# Microcontroller_rev2.net
KiCad netlist of a schematic drawn in Altium Designer
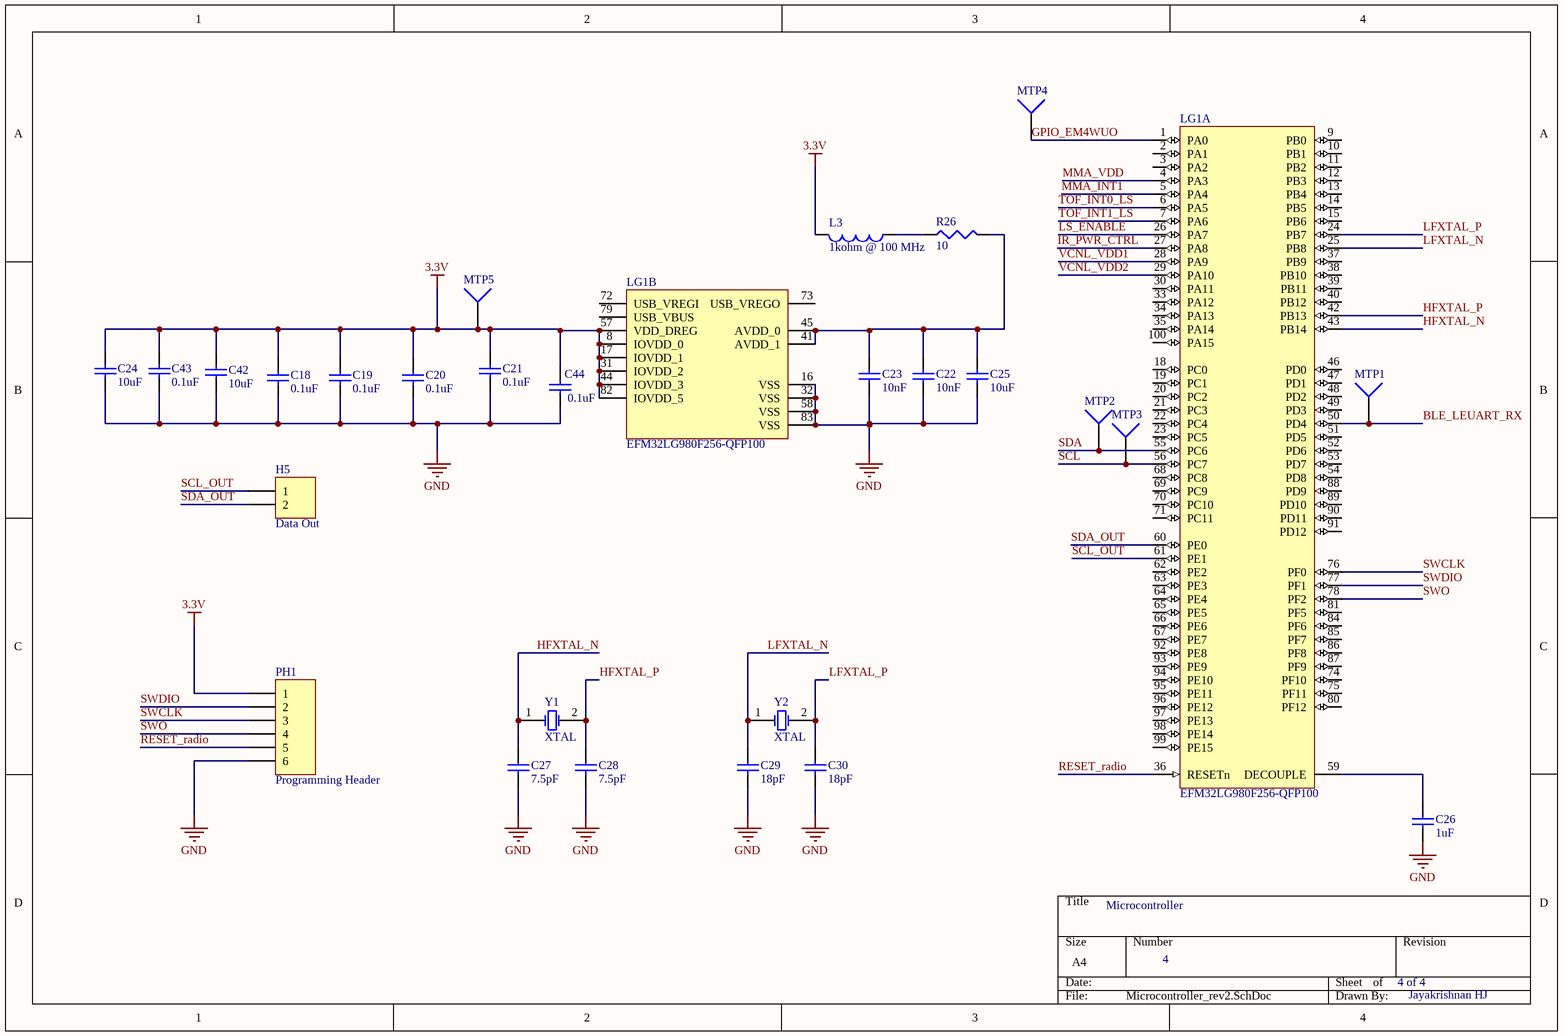
[diagram p0: Microcontroller_rev2.SchDoc]

(export (version "E")
  (design (tool "Eeschema 10.0.6"))
  (components
    (comp (ref "C18")
      (value "0.1uF")
      (footprint "1608[0603]")
      (description "CAP CER 0.1UF 10V X7R 0603")
      (fields (field (name "DIGIKEY PART NO") "399-1095-1-ND") (field (name "MANUFACTURER") "KEMET"))
      (libsource (lib "Miscellaneous Devices") (part "Cap Semi"))
    )
    (comp (ref "C19")
      (value "0.1uF")
      (footprint "1608[0603]")
      (description "CAP CER 0.1UF 10V X7R 0603")
      (fields (field (name "DIGIKEY PART NO") "399-1095-1-ND") (field (name "MANUFACTURER") "KEMET"))
      (libsource (lib "Miscellaneous Devices") (part "Cap Semi"))
    )
    (comp (ref "C20")
      (value "0.1uF")
      (footprint "1608[0603]")
      (description "CAP CER 0.1UF 10V X7R 0603")
      (fields (field (name "DIGIKEY PART NO") "399-1095-1-ND") (field (name "MANUFACTURER") "KEMET"))
      (libsource (lib "Miscellaneous Devices") (part "Cap Semi"))
    )
    (comp (ref "C21")
      (value "0.1uF")
      (footprint "1608[0603]")
      (description "CAP CER 0.1UF 10V X7R 0603")
      (fields (field (name "DIGIKEY PART NO") "399-1095-1-ND") (field (name "MANUFACTURER") "KEMET"))
      (libsource (lib "Miscellaneous Devices") (part "Cap Semi"))
    )
    (comp (ref "C22")
      (value "10nF")
      (footprint "1608[0603]")
      (description "CAP CER 10000PF 50V X7R 0603")
      (fields (field (name "DIGIKEY PART NO") "311-1085-1-ND") (field (name "MANUFACTURER") "Yageo"))
      (libsource (lib "Miscellaneous Devices") (part "Cap Semi"))
    )
    (comp (ref "C23")
      (value "10nF")
      (footprint "1608[0603]")
      (description "CAP CER 10000PF 50V X7R 0603")
      (fields (field (name "DIGIKEY PART NO") "311-1085-1-ND") (field (name "MANUFACTURER") "Yageo"))
      (libsource (lib "Miscellaneous Devices") (part "Cap Semi"))
    )
    (comp (ref "C24")
      (value "10uF")
      (footprint "1608[0603]")
      (description "CAP CER 10UF 10V X5R 0603")
      (fields
        (field (name "DIGIKEY PART NO") "490-10474-1-ND")
        (field (name "MANUFACTURER") "Murata Electronics North America")
      )
      (libsource (lib "Miscellaneous Devices") (part "Cap Semi"))
    )
    (comp (ref "C25")
      (value "10uF")
      (footprint "1608[0603]")
      (description "CAP CER 10UF 10V X5R 0603")
      (fields
        (field (name "DIGIKEY PART NO") "490-10474-1-ND")
        (field (name "MANUFACTURER") "Murata Electronics North America")
      )
      (libsource (lib "Miscellaneous Devices") (part "Cap Semi"))
    )
    (comp (ref "C26")
      (value "1uF")
      (footprint "1608[0603]")
      (description "CAP CER 1UF 10V X7R 0603")
      (fields
        (field (name "DIGIKEY PART NO") "1276-1946-1-ND")
        (field (name "MANUFACTURER") "Samsung Electro-Mechanics America, Inc.")
      )
      (libsource (lib "Miscellaneous Devices") (part "Cap Semi"))
    )
    (comp (ref "C27")
      (value "7.5pF")
      (footprint "1608[0603]")
      (description "Multilayer Ceramic Capacitors MLCC - SMD/SMT 25V 7.5pF C0G 0201 .1pF Tol")
      (fields (field (name "MOUSER PART NO") "581-02013A7R5BAT2A") (field (name "MANUFACTURER") "AVX"))
      (libsource (lib "Miscellaneous Devices") (part "Cap Semi"))
    )
    (comp (ref "C28")
      (value "7.5pF")
      (footprint "1608[0603]")
      (description "Multilayer Ceramic Capacitors MLCC - SMD/SMT 25V 7.5pF C0G 0201 .1pF Tol")
      (fields (field (name "MOUSER PART NO") "581-02013A7R5BAT2A") (field (name "MANUFACTURER") "AVX"))
      (libsource (lib "Miscellaneous Devices") (part "Cap Semi"))
    )
    (comp (ref "C29")
      (value "18pF")
      (footprint "1608[0603]")
      (description "CAP CER 18PF 250V NP0 0603")
      (fields
        (field (name "DIGIKEY PART NO") "712-1321-1-ND")
        (field (name "MANUFACTURER") "Johanson Technology Inc.")
      )
      (libsource (lib "Miscellaneous Devices") (part "Cap Semi"))
    )
    (comp (ref "C30")
      (value "18pF")
      (footprint "1608[0603]")
      (description "CAP CER 18PF 250V NP0 0603")
      (fields
        (field (name "DIGIKEY PART NO") "712-1321-1-ND")
        (field (name "MANUFACTURER") "Johanson Technology Inc.")
      )
      (libsource (lib "Miscellaneous Devices") (part "Cap Semi"))
    )
    (comp (ref "C42")
      (value "10uF")
      (footprint "1608[0603]")
      (description "CAP CER 10UF 10V X5R 0603")
      (fields
        (field (name "DIGIKEY PART NO") "490-10474-1-ND")
        (field (name "MANUFACTURER") "Murata Electronics North America")
      )
      (libsource (lib "Miscellaneous Devices") (part "Cap Semi"))
    )
    (comp (ref "C43")
      (value "0.1uF")
      (footprint "1608[0603]")
      (description "CAP CER 0.1UF 10V X7R 0603")
      (fields (field (name "DIGIKEY PART NO") "399-1095-1-ND") (field (name "MANUFACTURER") "KEMET"))
      (libsource (lib "Miscellaneous Devices") (part "Cap Semi"))
    )
    (comp (ref "C44")
      (value "0.1uF")
      (footprint "1608[0603]")
      (description "CAP CER 0.1UF 10V X7R 0603")
      (fields (field (name "DIGIKEY PART NO") "399-1095-1-ND") (field (name "MANUFACTURER") "KEMET"))
      (libsource (lib "Miscellaneous Devices") (part "Cap Semi"))
    )
    (comp (ref "H5")
      (value "Data Out")
      (footprint "HDR1X2")
      (description "Header, 2-Pin")
      (fields (field (name "PUBLISHER") "Altium Limited"))
      (libsource (lib "Miscellaneous Connectors") (part "Header 2"))
    )
    (comp (ref "L3")
      (value "1kohm @ 100 MHz")
      (footprint "6-0805_M")
      (description "FERRITE BEAD 1 KOHM 0805 1LN")
      (fields
        (field (name "DIGIKEY PART NO") "490-1047-1-ND")
        (field (name "MANUFACTURER") "Murata Electronics North America")
      )
      (libsource (lib "Miscellaneous Devices") (part "Inductor"))
    )
    (comp (ref "LG1")
      (value "EFM32LG980F256-QFP100")
      (footprint "ENMR-LQFP100_M")
      (description "ARM Microcontrollers - MCU 256k Flash 32k RAM USB 8x34 LCD AES")
      (fields
        (field (name "MOUSER PART NO") "634-EFM32LG980F256GE")
        (field (name "MANUFACTURER") "Silicon Labs")
        (field (name "MANUFACTURER PART NUMBER") "EFM32LG980F256G-E-QFP100")
      )
      (libsource (lib "Robonauts_parts") (part "EFM32LG980F256-QFP100"))
    )
    (comp (ref "MTP1")
      (value "Socket")
      (footprint "PIN1")
      (fields (field (name "PUBLISHER") "Altium Limited"))
      (libsource (lib "Miscellaneous Connectors") (part "Socket"))
    )
    (comp (ref "MTP2")
      (value "Socket")
      (footprint "PIN1")
      (fields (field (name "PUBLISHER") "Altium Limited"))
      (libsource (lib "Miscellaneous Connectors") (part "Socket"))
    )
    (comp (ref "MTP3")
      (value "Socket")
      (footprint "PIN1")
      (fields (field (name "PUBLISHER") "Altium Limited"))
      (libsource (lib "Miscellaneous Connectors") (part "Socket"))
    )
    (comp (ref "MTP4")
      (value "Socket")
      (footprint "PIN1")
      (fields (field (name "PUBLISHER") "Altium Limited"))
      (libsource (lib "Miscellaneous Connectors") (part "Socket"))
    )
    (comp (ref "MTP5")
      (value "Socket")
      (footprint "PIN1")
      (fields (field (name "PUBLISHER") "Altium Limited"))
      (libsource (lib "Miscellaneous Connectors") (part "Socket"))
    )
    (comp (ref "PH1")
      (value "Programming Header")
      (footprint "HDR1X6")
      (description "Header, 6-Pin")
      (libsource (lib "Miscellaneous Connectors") (part "Header 6"))
    )
    (comp (ref "R26")
      (value "10")
      (footprint "J1-0603")
      (description "RES SMD 10 OHM 1% 1/10W 0603")
      (fields (field (name "DIGIKEY PART NO") "311-10.0HRCT-ND") (field (name "MANUFACTURER") "Yageo"))
      (libsource (lib "Miscellaneous Devices") (part "Res3"))
    )
    (comp (ref "Y1")
      (value "XTAL")
      (footprint "Clock_LFXTAL")
      (description "Crystal Oscillator")
      (fields (field (name "PUBLISHER") "Altium Limited"))
      (libsource (lib "Miscellaneous Devices") (part "XTAL"))
    )
    (comp (ref "Y2")
      (value "XTAL")
      (footprint "Clock_LFXTAL")
      (description "CRYSTAL 32.7680KHZ 12.5PF SMD")
      (fields
        (field (name "MANUFACTURER") "Abracon LLC")
        (field (name "MANUFACTURER PART NUMBER") "AB26TRQ-32.768KHZ-T")
      )
      (libsource (lib "Miscellaneous Devices") (part "XTAL"))
    )
  )
  (nets
    (net (code "1") (name "/BLE_LEUART_RX") (class "Default")
      (node (ref "LG1") (pin "50") (pinfunction "PD4_50") (pintype "bidirectional"))
      (node (ref "MTP1") (pin "1") (pinfunction "1_1") (pintype "passive"))
    )
    (net (code "2") (name "/GPIO_EM4WUO") (class "Default")
      (node (ref "LG1") (pin "1") (pinfunction "PA0_1") (pintype "bidirectional"))
      (node (ref "MTP4") (pin "1") (pinfunction "1_1") (pintype "passive"))
    )
    (net (code "3") (name "/HFXTAL_N") (class "Default")
      (node (ref "C27") (pin "2") (pinfunction "2_2") (pintype "passive"))
      (node (ref "LG1") (pin "43") (pinfunction "PB14_43") (pintype "bidirectional"))
      (node (ref "Y1") (pin "1") (pinfunction "OSC1_1") (pintype "passive"))
    )
    (net (code "4") (name "/HFXTAL_P") (class "Default")
      (node (ref "C28") (pin "2") (pinfunction "2_2") (pintype "passive"))
      (node (ref "LG1") (pin "42") (pinfunction "PB13_42") (pintype "bidirectional"))
      (node (ref "Y1") (pin "2") (pinfunction "OSC2_2") (pintype "passive"))
    )
    (net (code "5") (name "/IR_PWR_CTRL") (class "Default")
      (node (ref "LG1") (pin "27") (pinfunction "PA8_27") (pintype "bidirectional"))
    )
    (net (code "6") (name "/LFXTAL_N") (class "Default")
      (node (ref "C29") (pin "2") (pinfunction "2_2") (pintype "passive"))
      (node (ref "LG1") (pin "25") (pinfunction "PB8_25") (pintype "bidirectional"))
      (node (ref "Y2") (pin "1") (pinfunction "OSC1_1") (pintype "passive"))
    )
    (net (code "7") (name "/LFXTAL_P") (class "Default")
      (node (ref "C30") (pin "2") (pinfunction "2_2") (pintype "passive"))
      (node (ref "LG1") (pin "24") (pinfunction "PB7_24") (pintype "bidirectional"))
      (node (ref "Y2") (pin "2") (pinfunction "OSC2_2") (pintype "passive"))
    )
    (net (code "8") (name "/LS_ENABLE") (class "Default")
      (node (ref "LG1") (pin "26") (pinfunction "PA7_26") (pintype "bidirectional"))
    )
    (net (code "9") (name "/MMA_INT1") (class "Default")
      (node (ref "LG1") (pin "5") (pinfunction "PA4_5") (pintype "bidirectional"))
    )
    (net (code "10") (name "/MMA_VDD") (class "Default")
      (node (ref "LG1") (pin "4") (pinfunction "PA3_4") (pintype "bidirectional"))
    )
    (net (code "11") (name "/RESET_radio") (class "Default")
      (node (ref "LG1") (pin "36") (pinfunction "RESETn_36") (pintype "input"))
      (node (ref "PH1") (pin "5") (pinfunction "5_5") (pintype "passive"))
    )
    (net (code "12") (name "/SCL") (class "Default")
      (node (ref "LG1") (pin "56") (pinfunction "PC7_56") (pintype "bidirectional"))
      (node (ref "MTP3") (pin "1") (pinfunction "1_1") (pintype "passive"))
    )
    (net (code "13") (name "/SCL_OUT") (class "Default")
      (node (ref "H5") (pin "1") (pinfunction "1_1") (pintype "passive"))
      (node (ref "LG1") (pin "61") (pinfunction "PE1_61") (pintype "bidirectional"))
    )
    (net (code "14") (name "/SDA") (class "Default")
      (node (ref "LG1") (pin "55") (pinfunction "PC6_55") (pintype "bidirectional"))
      (node (ref "MTP2") (pin "1") (pinfunction "1_1") (pintype "passive"))
    )
    (net (code "15") (name "/SDA_OUT") (class "Default")
      (node (ref "H5") (pin "2") (pinfunction "2_2") (pintype "passive"))
      (node (ref "LG1") (pin "60") (pinfunction "PE0_60") (pintype "bidirectional"))
    )
    (net (code "16") (name "/SWCLK") (class "Default")
      (node (ref "LG1") (pin "76") (pinfunction "PF0_76") (pintype "bidirectional"))
      (node (ref "PH1") (pin "3") (pinfunction "3_3") (pintype "passive"))
    )
    (net (code "17") (name "/SWDIO") (class "Default")
      (node (ref "LG1") (pin "77") (pinfunction "PF1_77") (pintype "bidirectional"))
      (node (ref "PH1") (pin "2") (pinfunction "2_2") (pintype "passive"))
    )
    (net (code "18") (name "/SWO") (class "Default")
      (node (ref "LG1") (pin "78") (pinfunction "PF2_78") (pintype "bidirectional"))
      (node (ref "PH1") (pin "4") (pinfunction "4_4") (pintype "passive"))
    )
    (net (code "19") (name "/TOF_INT0_LS") (class "Default")
      (node (ref "LG1") (pin "6") (pinfunction "PA5_6") (pintype "bidirectional"))
    )
    (net (code "20") (name "/TOF_INT1_LS") (class "Default")
      (node (ref "LG1") (pin "7") (pinfunction "PA6_7") (pintype "bidirectional"))
    )
    (net (code "21") (name "/VCNL_VDD1") (class "Default")
      (node (ref "LG1") (pin "28") (pinfunction "PA9_28") (pintype "bidirectional"))
    )
    (net (code "22") (name "/VCNL_VDD2") (class "Default")
      (node (ref "LG1") (pin "29") (pinfunction "PA10_29") (pintype "bidirectional"))
    )
    (net (code "23") (name "3.3V") (class "Default")
      (node (ref "C18") (pin "2") (pinfunction "2_2") (pintype "passive"))
      (node (ref "C19") (pin "2") (pinfunction "2_2") (pintype "passive"))
      (node (ref "C20") (pin "2") (pinfunction "2_2") (pintype "passive"))
      (node (ref "C21") (pin "2") (pinfunction "2_2") (pintype "passive"))
      (node (ref "C24") (pin "2") (pinfunction "2_2") (pintype "passive"))
      (node (ref "C42") (pin "2") (pinfunction "2_2") (pintype "passive"))
      (node (ref "C43") (pin "2") (pinfunction "2_2") (pintype "passive"))
      (node (ref "C44") (pin "2") (pinfunction "2_2") (pintype "passive"))
      (node (ref "L3") (pin "2") (pinfunction "2_2") (pintype "passive"))
      (node (ref "LG1") (pin "17") (pinfunction "IOVDD_1_17") (pintype "power_in"))
      (node (ref "LG1") (pin "31") (pinfunction "IOVDD_2_31") (pintype "power_in"))
      (node (ref "LG1") (pin "44") (pinfunction "IOVDD_3_44") (pintype "power_in"))
      (node (ref "LG1") (pin "57") (pinfunction "VDD_DREG_57") (pintype "power_in"))
      (node (ref "LG1") (pin "8") (pinfunction "IOVDD_0_8") (pintype "power_in"))
      (node (ref "LG1") (pin "82") (pinfunction "IOVDD_5_82") (pintype "power_in"))
      (node (ref "MTP5") (pin "1") (pinfunction "1_1") (pintype "passive"))
      (node (ref "PH1") (pin "1") (pinfunction "1_1") (pintype "passive"))
    )
    (net (code "24") (name "GND") (class "Default")
      (node (ref "C18") (pin "1") (pinfunction "1_1") (pintype "passive"))
      (node (ref "C19") (pin "1") (pinfunction "1_1") (pintype "passive"))
      (node (ref "C20") (pin "1") (pinfunction "1_1") (pintype "passive"))
      (node (ref "C21") (pin "1") (pinfunction "1_1") (pintype "passive"))
      (node (ref "C22") (pin "1") (pinfunction "1_1") (pintype "passive"))
      (node (ref "C23") (pin "1") (pinfunction "1_1") (pintype "passive"))
      (node (ref "C24") (pin "1") (pinfunction "1_1") (pintype "passive"))
      (node (ref "C25") (pin "1") (pinfunction "1_1") (pintype "passive"))
      (node (ref "C26") (pin "1") (pinfunction "1_1") (pintype "passive"))
      (node (ref "C27") (pin "1") (pinfunction "1_1") (pintype "passive"))
      (node (ref "C28") (pin "1") (pinfunction "1_1") (pintype "passive"))
      (node (ref "C29") (pin "1") (pinfunction "1_1") (pintype "passive"))
      (node (ref "C30") (pin "1") (pinfunction "1_1") (pintype "passive"))
      (node (ref "C42") (pin "1") (pinfunction "1_1") (pintype "passive"))
      (node (ref "C43") (pin "1") (pinfunction "1_1") (pintype "passive"))
      (node (ref "C44") (pin "1") (pinfunction "1_1") (pintype "passive"))
      (node (ref "LG1") (pin "16") (pinfunction "VSS_16") (pintype "power_in"))
      (node (ref "LG1") (pin "32") (pinfunction "VSS_32") (pintype "power_in"))
      (node (ref "LG1") (pin "58") (pinfunction "VSS_58") (pintype "power_in"))
      (node (ref "LG1") (pin "83") (pinfunction "VSS_83") (pintype "power_in"))
      (node (ref "PH1") (pin "6") (pinfunction "6_6") (pintype "passive"))
    )
    (net (code "25") (name "Net-(L3-Pad1)") (class "Default")
      (node (ref "L3") (pin "1") (pinfunction "1_1") (pintype "passive"))
      (node (ref "R26") (pin "1") (pinfunction "1_1") (pintype "passive"))
    )
    (net (code "26") (name "Net-(LG1A-DECOUPLE)") (class "Default")
      (node (ref "C26") (pin "2") (pinfunction "2_2") (pintype "passive"))
      (node (ref "LG1") (pin "59") (pinfunction "DECOUPLE_59") (pintype "passive"))
    )
    (net (code "27") (name "Net-(LG1B-AVDD_0)") (class "Default")
      (node (ref "C22") (pin "2") (pinfunction "2_2") (pintype "passive"))
      (node (ref "C23") (pin "2") (pinfunction "2_2") (pintype "passive"))
      (node (ref "C25") (pin "2") (pinfunction "2_2") (pintype "passive"))
      (node (ref "LG1") (pin "41") (pinfunction "AVDD_1_41") (pintype "power_in"))
      (node (ref "LG1") (pin "45") (pinfunction "AVDD_0_45") (pintype "power_in"))
      (node (ref "R26") (pin "2") (pinfunction "2_2") (pintype "passive"))
    )
    (net (code "28") (name "unconnected-(LG1A-PA1-Pad2)") (class "Default")
      (node (ref "LG1") (pin "2") (pinfunction "PA1_2") (pintype "bidirectional"))
    )
    (net (code "29") (name "unconnected-(LG1A-PA2-Pad3)") (class "Default")
      (node (ref "LG1") (pin "3") (pinfunction "PA2_3") (pintype "bidirectional"))
    )
    (net (code "30") (name "unconnected-(LG1A-PA11-Pad30)") (class "Default")
      (node (ref "LG1") (pin "30") (pinfunction "PA11_30") (pintype "bidirectional"))
    )
    (net (code "31") (name "unconnected-(LG1A-PA12-Pad33)") (class "Default")
      (node (ref "LG1") (pin "33") (pinfunction "PA12_33") (pintype "bidirectional"))
    )
    (net (code "32") (name "unconnected-(LG1A-PA13-Pad34)") (class "Default")
      (node (ref "LG1") (pin "34") (pinfunction "PA13_34") (pintype "bidirectional"))
    )
    (net (code "33") (name "unconnected-(LG1A-PA14-Pad35)") (class "Default")
      (node (ref "LG1") (pin "35") (pinfunction "PA14_35") (pintype "bidirectional"))
    )
    (net (code "34") (name "unconnected-(LG1A-PA15-Pad100)") (class "Default")
      (node (ref "LG1") (pin "100") (pinfunction "PA15_100") (pintype "bidirectional"))
    )
    (net (code "35") (name "unconnected-(LG1A-PB0-Pad9)") (class "Default")
      (node (ref "LG1") (pin "9") (pinfunction "PB0_9") (pintype "bidirectional"))
    )
    (net (code "36") (name "unconnected-(LG1A-PB1-Pad10)") (class "Default")
      (node (ref "LG1") (pin "10") (pinfunction "PB1_10") (pintype "bidirectional"))
    )
    (net (code "37") (name "unconnected-(LG1A-PB2-Pad11)") (class "Default")
      (node (ref "LG1") (pin "11") (pinfunction "PB2_11") (pintype "bidirectional"))
    )
    (net (code "38") (name "unconnected-(LG1A-PB3-Pad12)") (class "Default")
      (node (ref "LG1") (pin "12") (pinfunction "PB3_12") (pintype "bidirectional"))
    )
    (net (code "39") (name "unconnected-(LG1A-PB4-Pad13)") (class "Default")
      (node (ref "LG1") (pin "13") (pinfunction "PB4_13") (pintype "bidirectional"))
    )
    (net (code "40") (name "unconnected-(LG1A-PB5-Pad14)") (class "Default")
      (node (ref "LG1") (pin "14") (pinfunction "PB5_14") (pintype "bidirectional"))
    )
    (net (code "41") (name "unconnected-(LG1A-PB6-Pad15)") (class "Default")
      (node (ref "LG1") (pin "15") (pinfunction "PB6_15") (pintype "bidirectional"))
    )
    (net (code "42") (name "unconnected-(LG1A-PB9-Pad37)") (class "Default")
      (node (ref "LG1") (pin "37") (pinfunction "PB9_37") (pintype "bidirectional"))
    )
    (net (code "43") (name "unconnected-(LG1A-PB10-Pad38)") (class "Default")
      (node (ref "LG1") (pin "38") (pinfunction "PB10_38") (pintype "bidirectional"))
    )
    (net (code "44") (name "unconnected-(LG1A-PB11-Pad39)") (class "Default")
      (node (ref "LG1") (pin "39") (pinfunction "PB11_39") (pintype "bidirectional"))
    )
    (net (code "45") (name "unconnected-(LG1A-PB12-Pad40)") (class "Default")
      (node (ref "LG1") (pin "40") (pinfunction "PB12_40") (pintype "bidirectional"))
    )
    (net (code "46") (name "unconnected-(LG1A-PC0-Pad18)") (class "Default")
      (node (ref "LG1") (pin "18") (pinfunction "PC0_18") (pintype "bidirectional"))
    )
    (net (code "47") (name "unconnected-(LG1A-PC1-Pad19)") (class "Default")
      (node (ref "LG1") (pin "19") (pinfunction "PC1_19") (pintype "bidirectional"))
    )
    (net (code "48") (name "unconnected-(LG1A-PC2-Pad20)") (class "Default")
      (node (ref "LG1") (pin "20") (pinfunction "PC2_20") (pintype "bidirectional"))
    )
    (net (code "49") (name "unconnected-(LG1A-PC3-Pad21)") (class "Default")
      (node (ref "LG1") (pin "21") (pinfunction "PC3_21") (pintype "bidirectional"))
    )
    (net (code "50") (name "unconnected-(LG1A-PC4-Pad22)") (class "Default")
      (node (ref "LG1") (pin "22") (pinfunction "PC4_22") (pintype "bidirectional"))
    )
    (net (code "51") (name "unconnected-(LG1A-PC5-Pad23)") (class "Default")
      (node (ref "LG1") (pin "23") (pinfunction "PC5_23") (pintype "bidirectional"))
    )
    (net (code "52") (name "unconnected-(LG1A-PC8-Pad68)") (class "Default")
      (node (ref "LG1") (pin "68") (pinfunction "PC8_68") (pintype "bidirectional"))
    )
    (net (code "53") (name "unconnected-(LG1A-PC9-Pad69)") (class "Default")
      (node (ref "LG1") (pin "69") (pinfunction "PC9_69") (pintype "bidirectional"))
    )
    (net (code "54") (name "unconnected-(LG1A-PC10-Pad70)") (class "Default")
      (node (ref "LG1") (pin "70") (pinfunction "PC10_70") (pintype "bidirectional"))
    )
    (net (code "55") (name "unconnected-(LG1A-PC11-Pad71)") (class "Default")
      (node (ref "LG1") (pin "71") (pinfunction "PC11_71") (pintype "bidirectional"))
    )
    (net (code "56") (name "unconnected-(LG1A-PD0-Pad46)") (class "Default")
      (node (ref "LG1") (pin "46") (pinfunction "PD0_46") (pintype "bidirectional"))
    )
    (net (code "57") (name "unconnected-(LG1A-PD1-Pad47)") (class "Default")
      (node (ref "LG1") (pin "47") (pinfunction "PD1_47") (pintype "bidirectional"))
    )
    (net (code "58") (name "unconnected-(LG1A-PD2-Pad48)") (class "Default")
      (node (ref "LG1") (pin "48") (pinfunction "PD2_48") (pintype "bidirectional"))
    )
    (net (code "59") (name "unconnected-(LG1A-PD3-Pad49)") (class "Default")
      (node (ref "LG1") (pin "49") (pinfunction "PD3_49") (pintype "bidirectional"))
    )
    (net (code "60") (name "unconnected-(LG1A-PD5-Pad51)") (class "Default")
      (node (ref "LG1") (pin "51") (pinfunction "PD5_51") (pintype "bidirectional"))
    )
    (net (code "61") (name "unconnected-(LG1A-PD6-Pad52)") (class "Default")
      (node (ref "LG1") (pin "52") (pinfunction "PD6_52") (pintype "bidirectional"))
    )
    (net (code "62") (name "unconnected-(LG1A-PD7-Pad53)") (class "Default")
      (node (ref "LG1") (pin "53") (pinfunction "PD7_53") (pintype "bidirectional"))
    )
    (net (code "63") (name "unconnected-(LG1A-PD8-Pad54)") (class "Default")
      (node (ref "LG1") (pin "54") (pinfunction "PD8_54") (pintype "bidirectional"))
    )
    (net (code "64") (name "unconnected-(LG1A-PD9-Pad88)") (class "Default")
      (node (ref "LG1") (pin "88") (pinfunction "PD9_88") (pintype "bidirectional"))
    )
    (net (code "65") (name "unconnected-(LG1A-PD10-Pad89)") (class "Default")
      (node (ref "LG1") (pin "89") (pinfunction "PD10_89") (pintype "bidirectional"))
    )
    (net (code "66") (name "unconnected-(LG1A-PD11-Pad90)") (class "Default")
      (node (ref "LG1") (pin "90") (pinfunction "PD11_90") (pintype "bidirectional"))
    )
    (net (code "67") (name "unconnected-(LG1A-PD12-Pad91)") (class "Default")
      (node (ref "LG1") (pin "91") (pinfunction "PD12_91") (pintype "bidirectional"))
    )
    (net (code "68") (name "unconnected-(LG1A-PE2-Pad62)") (class "Default")
      (node (ref "LG1") (pin "62") (pinfunction "PE2_62") (pintype "bidirectional"))
    )
    (net (code "69") (name "unconnected-(LG1A-PE3-Pad63)") (class "Default")
      (node (ref "LG1") (pin "63") (pinfunction "PE3_63") (pintype "bidirectional"))
    )
    (net (code "70") (name "unconnected-(LG1A-PE4-Pad64)") (class "Default")
      (node (ref "LG1") (pin "64") (pinfunction "PE4_64") (pintype "bidirectional"))
    )
    (net (code "71") (name "unconnected-(LG1A-PE5-Pad65)") (class "Default")
      (node (ref "LG1") (pin "65") (pinfunction "PE5_65") (pintype "bidirectional"))
    )
    (net (code "72") (name "unconnected-(LG1A-PE6-Pad66)") (class "Default")
      (node (ref "LG1") (pin "66") (pinfunction "PE6_66") (pintype "bidirectional"))
    )
    (net (code "73") (name "unconnected-(LG1A-PE7-Pad67)") (class "Default")
      (node (ref "LG1") (pin "67") (pinfunction "PE7_67") (pintype "bidirectional"))
    )
    (net (code "74") (name "unconnected-(LG1A-PE8-Pad92)") (class "Default")
      (node (ref "LG1") (pin "92") (pinfunction "PE8_92") (pintype "bidirectional"))
    )
    (net (code "75") (name "unconnected-(LG1A-PE9-Pad93)") (class "Default")
      (node (ref "LG1") (pin "93") (pinfunction "PE9_93") (pintype "bidirectional"))
    )
    (net (code "76") (name "unconnected-(LG1A-PE10-Pad94)") (class "Default")
      (node (ref "LG1") (pin "94") (pinfunction "PE10_94") (pintype "bidirectional"))
    )
    (net (code "77") (name "unconnected-(LG1A-PE11-Pad95)") (class "Default")
      (node (ref "LG1") (pin "95") (pinfunction "PE11_95") (pintype "bidirectional"))
    )
    (net (code "78") (name "unconnected-(LG1A-PE12-Pad96)") (class "Default")
      (node (ref "LG1") (pin "96") (pinfunction "PE12_96") (pintype "bidirectional"))
    )
    (net (code "79") (name "unconnected-(LG1A-PE13-Pad97)") (class "Default")
      (node (ref "LG1") (pin "97") (pinfunction "PE13_97") (pintype "bidirectional"))
    )
    (net (code "80") (name "unconnected-(LG1A-PE14-Pad98)") (class "Default")
      (node (ref "LG1") (pin "98") (pinfunction "PE14_98") (pintype "bidirectional"))
    )
    (net (code "81") (name "unconnected-(LG1A-PE15-Pad99)") (class "Default")
      (node (ref "LG1") (pin "99") (pinfunction "PE15_99") (pintype "bidirectional"))
    )
    (net (code "82") (name "unconnected-(LG1A-PF5-Pad81)") (class "Default")
      (node (ref "LG1") (pin "81") (pinfunction "PF5_81") (pintype "bidirectional"))
    )
    (net (code "83") (name "unconnected-(LG1A-PF6-Pad84)") (class "Default")
      (node (ref "LG1") (pin "84") (pinfunction "PF6_84") (pintype "bidirectional"))
    )
    (net (code "84") (name "unconnected-(LG1A-PF7-Pad85)") (class "Default")
      (node (ref "LG1") (pin "85") (pinfunction "PF7_85") (pintype "bidirectional"))
    )
    (net (code "85") (name "unconnected-(LG1A-PF8-Pad86)") (class "Default")
      (node (ref "LG1") (pin "86") (pinfunction "PF8_86") (pintype "bidirectional"))
    )
    (net (code "86") (name "unconnected-(LG1A-PF9-Pad87)") (class "Default")
      (node (ref "LG1") (pin "87") (pinfunction "PF9_87") (pintype "bidirectional"))
    )
    (net (code "87") (name "unconnected-(LG1A-PF10-Pad74)") (class "Default")
      (node (ref "LG1") (pin "74") (pinfunction "PF10_74") (pintype "bidirectional"))
    )
    (net (code "88") (name "unconnected-(LG1A-PF11-Pad75)") (class "Default")
      (node (ref "LG1") (pin "75") (pinfunction "PF11_75") (pintype "bidirectional"))
    )
    (net (code "89") (name "unconnected-(LG1A-PF12-Pad80)") (class "Default")
      (node (ref "LG1") (pin "80") (pinfunction "PF12_80") (pintype "bidirectional"))
    )
    (net (code "90") (name "unconnected-(LG1B-USB_VBUS-Pad79)") (class "Default")
      (node (ref "LG1") (pin "79") (pinfunction "USB_VBUS_79") (pintype "power_in"))
    )
    (net (code "91") (name "unconnected-(LG1B-USB_VREGI-Pad72)") (class "Default")
      (node (ref "LG1") (pin "72") (pinfunction "USB_VREGI_72") (pintype "power_in"))
    )
    (net (code "92") (name "unconnected-(LG1B-USB_VREGO-Pad73)") (class "Default")
      (node (ref "LG1") (pin "73") (pinfunction "USB_VREGO_73") (pintype "passive"))
    )
  )
)
